# PowerSupply.net
KiCad netlist of a schematic drawn in Altium Designer
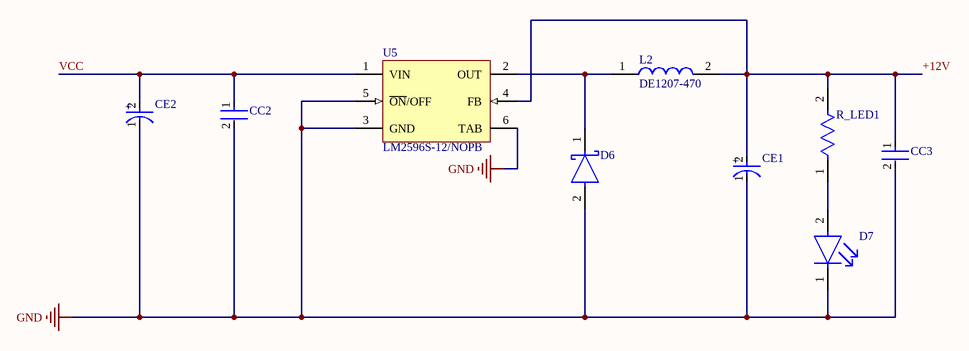
[diagram p0: PowerSupply.SchDoc]

(export (version "E")
  (design (tool "Eeschema 10.0.6"))
  (components
    (comp (ref "CC2")
      (value "12062C104K4T2A")
      (footprint "FP-1206-L_3_2_0_2-W_1_6_0-IPC_A")
      (description "Automotive Ceramic Capacitor, 1206, 100nF, 10%, X7R, 15%, 200V")
      (fields (field (name "TOLERANCE") "10%"))
      (libsource (lib "Altium Content Vault") (part "b4654b650e69147ec39a6b967a45e02"))
    )
    (comp (ref "CC3")
      (value "12062C104K4T2A")
      (footprint "FP-1206-L_3_2_0_2-W_1_6_0-IPC_A")
      (description "Automotive Ceramic Capacitor, 1206, 100nF, 10%, X7R, 15%, 200V")
      (fields (field (name "TOLERANCE") "10%"))
      (libsource (lib "Altium Content Vault") (part "b4654b650e69147ec39a6b967a45e02"))
    )
    (comp (ref "CE1")
      (value "EEV-FK2A221M")
      (footprint "FP-FKK16-MFG")
      (description "CAP ALUM 220UF 20% 100V SMD")
      (fields (field (name "TOLERANCE") "20%") (field (name "VOLTAGE") "100V"))
      (libsource (lib "Altium Content Vault") (part "203bc49f2ac43e59fd269a8c329ed05"))
    )
    (comp (ref "CE2")
      (value "50THV100M10X10.5")
      (footprint "FP-THV10X10_5-MFG")
      (description "CAP ALUM 100UF 20% 50V SMD")
      (fields (field (name "VOLTAGE") "50V") (field (name "TOLERANCE") "20%"))
      (libsource (lib "Altium Content Vault") (part "203bc49f2ac43e59fd269a8c329ed05"))
    )
    (comp (ref "D6")
      (value "SS34-E3/57T")
      (footprint "FP-95402-MFG")
      (description "DIODE SCHOTTKY 40V 3A DO214AB")
      (fields
        (field (name "MANUFACTURER") "Vishay")
        (field (name "OCTOPART") "https://octopart.com/ss34-e3%2F57t-vishay-39552907")
      )
      (libsource (lib "Altium Content Vault") (part "1d6ec82d83fb6aee721767c19dac4b9"))
    )
    (comp (ref "D7")
      (value "SML-LX0603SIW-TR")
      (footprint "FP-SML-LX0603SIW-TR-MFG")
      (description "LED RED DIFFUSED SMD")
      (libsource (lib "Altium Content Vault") (part "8706943c75ba83719d021d2fdc84c58"))
    )
    (comp (ref "L2")
      (value "DE1207-470")
      (footprint "SamacSys:DE1207330")
      (description "Inductor")
      (fields (field (name "MANUFACTURER_PART_NUMBER") "DE1207-330"))
      (libsource (lib "*") (part "DE1207-330"))
    )
    (comp (ref "R_LED1")
      (value "CRCW0805220RJNEA")
      (footprint "FP-CRCW0805-e3-IPC_A")
      (description "RES Thick Film, 220Ω, 5%, 0.125W, 200ppm/°C, 0805")
      (fields (field (name "TOLERANCE") "5%"))
      (libsource (lib "Altium Content Vault") (part "1029c3af85768c4190bb7ad29bc67b5"))
    )
    (comp (ref "U5")
      (value "LM2596S-12/NOPB")
      (footprint "KTT0005B_M")
      (description "SIMPLE SWITCHER® Power Converter 150 KHz 3A Step-Down Voltage Regulator, 5-pin TO-263, Pb-Free")
      (fields (field (name "MANUFACTURER") "Texas Instruments"))
      (libsource (lib "Altium Content Vault") (part "PM-REG-LM2575HVS-12"))
    )
  )
  (nets
    (net (code "1") (name "/+12V") (class "Default")
      (node (ref "CC3") (pin "1") (pinfunction "1_1") (pintype "passive"))
      (node (ref "CE1") (pin "2") (pinfunction "A_2") (pintype "passive"))
      (node (ref "L2") (pin "2") (pinfunction "2_2") (pintype "passive"))
      (node (ref "R_LED1") (pin "2") (pinfunction "2_2") (pintype "passive"))
      (node (ref "U5") (pin "4") (pinfunction "FB_4") (pintype "input"))
    )
    (net (code "2") (name "/VCC") (class "Default")
      (node (ref "CC2") (pin "1") (pinfunction "1_1") (pintype "passive"))
      (node (ref "CE2") (pin "2") (pinfunction "A_2") (pintype "passive"))
      (node (ref "U5") (pin "1") (pinfunction "VIN_1") (pintype "power_in"))
    )
    (net (code "3") (name "GND") (class "Default")
      (node (ref "CC2") (pin "2") (pinfunction "2_2") (pintype "passive"))
      (node (ref "CC3") (pin "2") (pinfunction "2_2") (pintype "passive"))
      (node (ref "CE1") (pin "1") (pinfunction "C_1") (pintype "passive"))
      (node (ref "CE2") (pin "1") (pinfunction "C_1") (pintype "passive"))
      (node (ref "D6") (pin "2") (pinfunction "A_2") (pintype "passive"))
      (node (ref "D7") (pin "1") (pinfunction "C_1") (pintype "passive"))
      (node (ref "U5") (pin "3") (pinfunction "GND_3") (pintype "power_in"))
      (node (ref "U5") (pin "5") (pinfunction "~{ON}/OFF_5") (pintype "input"))
      (node (ref "U5") (pin "6") (pinfunction "TAB_6") (pintype "power_in"))
    )
    (net (code "4") (name "Net-(D6-C)") (class "Default")
      (node (ref "D6") (pin "1") (pinfunction "C_1") (pintype "passive"))
      (node (ref "L2") (pin "1") (pinfunction "1_1") (pintype "passive"))
      (node (ref "U5") (pin "2") (pinfunction "OUT_2") (pintype "power_in"))
    )
    (net (code "5") (name "Net-(D7-A)") (class "Default")
      (node (ref "D7") (pin "2") (pinfunction "A_2") (pintype "passive"))
      (node (ref "R_LED1") (pin "1") (pinfunction "1_1") (pintype "passive"))
    )
  )
)
